# Enclosure_85x58.net
KiCad netlist of a schematic drawn in EAGLE
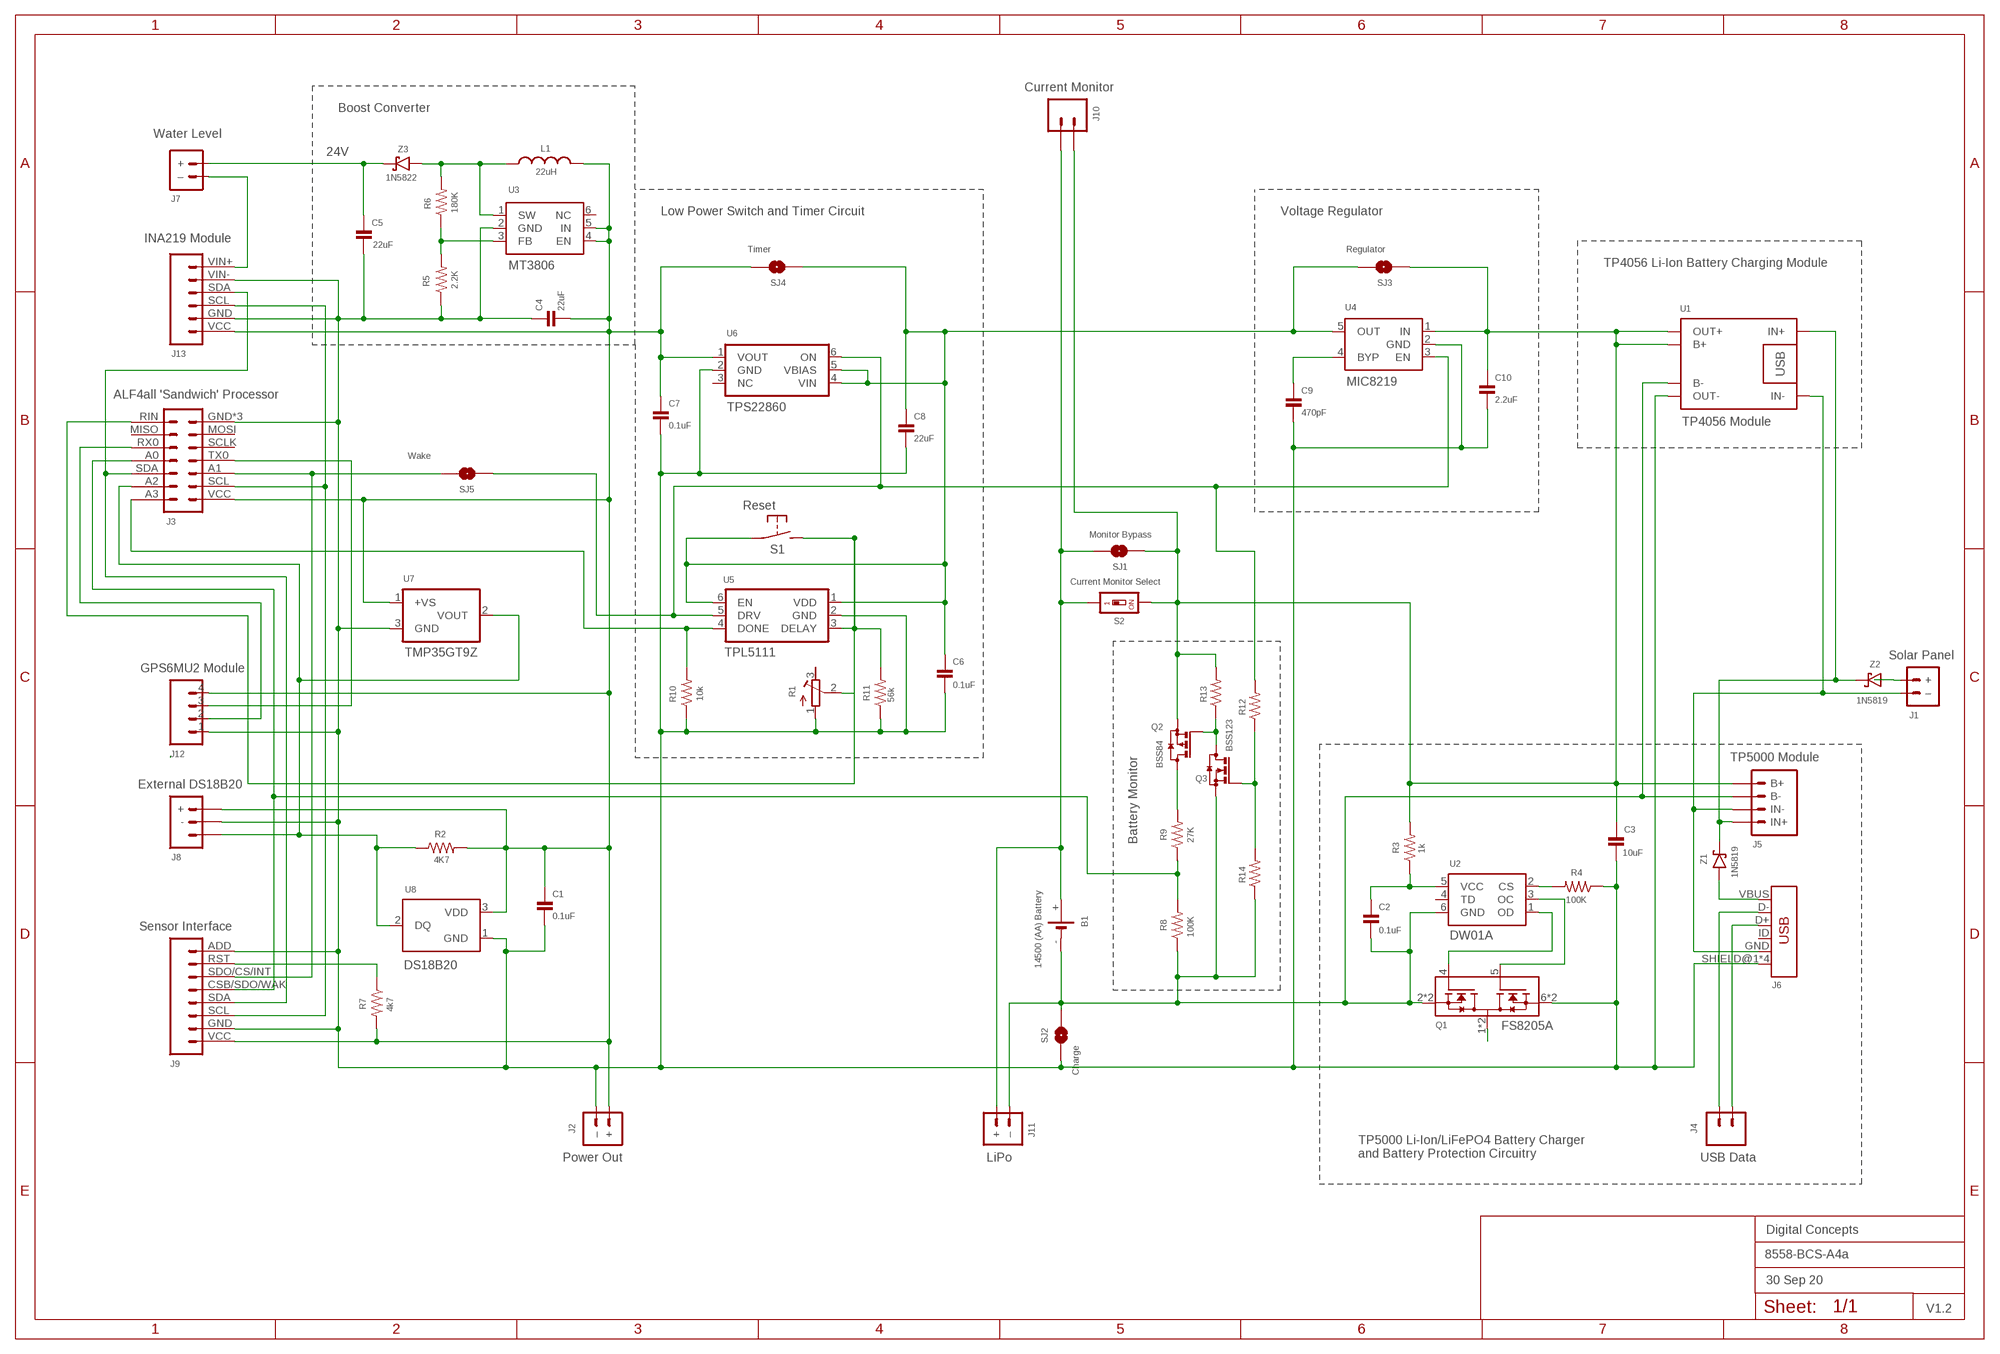
[diagram p0: schematic, sheet 1]

(export (version "E")
  (design (tool "Eeschema 10.0.6"))
  (components
    (comp (ref "B1")
      (value "14500 (AA) Battery")
      (footprint "eagle-import:BATTERY-14500")
      (libsource (lib "eagle-import") (part "BATTERY-HOLDER-14500(AA)"))
    )
    (comp (ref "C1")
      (value "0.1uF")
      (footprint "eagle-import:C0805-VIA-2")
      (libsource (lib "eagle-import") (part "CAPACITOR-VIA-2"))
    )
    (comp (ref "C2")
      (value "0.1uF")
      (footprint "eagle-import:C0805-VIA-1")
      (libsource (lib "eagle-import") (part "CAPACITOR-VIA-1"))
    )
    (comp (ref "C3")
      (value "10uF")
      (footprint "eagle-import:C0805-VIA-2")
      (libsource (lib "eagle-import") (part "CAPACITOR-VIA-2"))
    )
    (comp (ref "C4")
      (value "22uF")
      (footprint "eagle-import:C0805-VIA-1")
      (libsource (lib "eagle-import") (part "CAPACITOR-VIA-1"))
    )
    (comp (ref "C5")
      (value "22uF")
      (footprint "eagle-import:C0805")
      (libsource (lib "eagle-import") (part "CAPACITOR"))
    )
    (comp (ref "C6")
      (value "0.1uF")
      (footprint "eagle-import:C0805")
      (libsource (lib "eagle-import") (part "CAPACITOR"))
    )
    (comp (ref "C7")
      (value "0.1uF")
      (footprint "eagle-import:C0805-VIA-1")
      (libsource (lib "eagle-import") (part "CAPACITOR-VIA-1"))
    )
    (comp (ref "C8")
      (value "22uF")
      (footprint "eagle-import:C0805-VIA-2")
      (libsource (lib "eagle-import") (part "CAPACITOR-VIA-2"))
    )
    (comp (ref "C9")
      (value "470pF")
      (footprint "eagle-import:C0805")
      (libsource (lib "eagle-import") (part "CAPACITOR"))
    )
    (comp (ref "C10")
      (value "2.2uF")
      (footprint "eagle-import:C0805-VIA-2")
      (libsource (lib "eagle-import") (part "CAPACITOR-VIA-2"))
    )
    (comp (ref "J1")
      (value "Solar Panel")
      (footprint "eagle-import:JST-PH2.0-2-VERTICAL")
      (libsource (lib "eagle-import") (part "JST-PH2.0-2-MALE-VERTICAL"))
    )
    (comp (ref "J2")
      (value "Power Out")
      (footprint "eagle-import:JST-PH1.25-2")
      (libsource (lib "eagle-import") (part "JST-PH1.25-2-MALE"))
    )
    (comp (ref "J3")
      (value "ALF4all 'Sandwich' Processor")
      (footprint "eagle-import:CONN_2X7-ALF4ALL-PROCESSOR")
      (libsource (lib "eagle-import") (part "HEADER-2X7-ALF4ALL-PROCESSOR"))
    )
    (comp (ref "J4")
      (value "USB Data")
      (footprint "eagle-import:CONN_02-GENERIC")
      (libsource (lib "eagle-import") (part "1X2-PIN-HEADER"))
    )
    (comp (ref "J5")
      (value "TP5000 Module")
      (footprint "eagle-import:CONN_04-GENERIC")
      (libsource (lib "eagle-import") (part "TP5000-MODULE"))
    )
    (comp (ref "J6")
      (value "USB")
      (footprint "eagle-import:USB-MINIB")
      (libsource (lib "eagle-import") (part "USB_MINI-B_SMT"))
    )
    (comp (ref "J7")
      (value "Water Level")
      (footprint "eagle-import:JST-PH2.0-2-VERTICAL")
      (libsource (lib "eagle-import") (part "JST-PH2.0-2-MALE-VERTICAL"))
    )
    (comp (ref "J8")
      (value "External DS18B20")
      (footprint "eagle-import:JST-PH2.0-3-VERTICAL")
      (libsource (lib "eagle-import") (part "JST-PH2.0-3-MALE-VERTICAL"))
    )
    (comp (ref "J9")
      (value "Sensor Interface")
      (footprint "eagle-import:CONN_08-SENSOR")
      (libsource (lib "eagle-import") (part "HEADER-1X8-SENSOR"))
    )
    (comp (ref "J10")
      (value "Current Monitor")
      (footprint "eagle-import:JST-PH2.0-2-HORIZONTAL")
      (libsource (lib "eagle-import") (part "JST-PH2.0-2-MALE-HORIZONTALJST-PTH-2"))
    )
    (comp (ref "J11")
      (value "LiPo")
      (footprint "eagle-import:JST-PH2.0-2-VERTICAL")
      (libsource (lib "eagle-import") (part "JST-PH2.0-2-MALE-VERTICAL"))
    )
    (comp (ref "J12")
      (value "GPS6MU2 Module")
      (footprint "eagle-import:CONN_04-GENERIC")
      (libsource (lib "eagle-import") (part "HEADER-1X4-GENERIC"))
    )
    (comp (ref "J13")
      (value "INA219 Module")
      (footprint "eagle-import:CONN_06-INA219")
      (libsource (lib "eagle-import") (part "INA219-I2C-MODULE"))
    )
    (comp (ref "L1")
      (value "22uH")
      (footprint "eagle-import:L5038P")
      (libsource (lib "eagle-import") (part "INDUCTORL5038P"))
    )
    (comp (ref "Q1")
      (value "FS8205A")
      (footprint "eagle-import:SOP65P640X120-8N")
      (fields (field (name "MF") "Fortune Semiconductor"))
      (libsource (lib "eagle-import") (part "FS8205A"))
    )
    (comp (ref "Q2")
      (value "BSS84")
      (footprint "eagle-import:SOT23")
      (libsource (lib "eagle-import") (part "BSS84"))
    )
    (comp (ref "Q3")
      (value "BSS123")
      (footprint "eagle-import:SOT23")
      (libsource (lib "eagle-import") (part "BSS123"))
    )
    (comp (ref "R1")
      (value "RESISTOR-TRIMM64W")
      (footprint "eagle-import:RTRIM64W")
      (libsource (lib "eagle-import") (part "RESISTOR-TRIMM64W"))
    )
    (comp (ref "R2")
      (value "4K7")
      (footprint "eagle-import:R0805")
      (libsource (lib "eagle-import") (part "RESISTORR0805"))
    )
    (comp (ref "R3")
      (value "1k")
      (footprint "eagle-import:R0805")
      (libsource (lib "eagle-import") (part "RESISTORR0805"))
    )
    (comp (ref "R4")
      (value "100K")
      (footprint "eagle-import:R0805")
      (libsource (lib "eagle-import") (part "RESISTORR0805"))
    )
    (comp (ref "R5")
      (value "2.2K")
      (footprint "eagle-import:R0805-VIA-1")
      (libsource (lib "eagle-import") (part "RESISTOR-VIA-1"))
    )
    (comp (ref "R6")
      (value "180K")
      (footprint "eagle-import:R0805")
      (libsource (lib "eagle-import") (part "RESISTORR0805"))
    )
    (comp (ref "R7")
      (value "4k7")
      (footprint "eagle-import:R0805")
      (libsource (lib "eagle-import") (part "RESISTORR0805"))
    )
    (comp (ref "R8")
      (value "100K")
      (footprint "eagle-import:R0805")
      (libsource (lib "eagle-import") (part "RESISTORR0805"))
    )
    (comp (ref "R9")
      (value "27K")
      (footprint "eagle-import:R0805-VIA-12")
      (libsource (lib "eagle-import") (part "RESISTOR-VIA-12"))
    )
    (comp (ref "R10")
      (value "10k")
      (footprint "eagle-import:R0805-VIA-2")
      (libsource (lib "eagle-import") (part "RESISTOR-VIA-2"))
    )
    (comp (ref "R11")
      (value "56k")
      (footprint "eagle-import:R0805-VIA-1")
      (libsource (lib "eagle-import") (part "RESISTOR-VIA-1"))
    )
    (comp (ref "R12")
      (value "RESISTORR0805")
      (footprint "eagle-import:R0805")
      (libsource (lib "eagle-import") (part "RESISTORR0805"))
    )
    (comp (ref "R13")
      (value "RESISTORR0805")
      (footprint "eagle-import:R0805")
      (libsource (lib "eagle-import") (part "RESISTORR0805"))
    )
    (comp (ref "R14")
      (value "RESISTORR0805")
      (footprint "eagle-import:R0805")
      (libsource (lib "eagle-import") (part "RESISTORR0805"))
    )
    (comp (ref "S1")
      (value "Reset")
      (footprint "eagle-import:SWITCH-2-PAD-VIAS")
      (libsource (lib "eagle-import") (part "SWITCH-MOMENTARY-2-PIN-VIAS"))
    )
    (comp (ref "S2")
      (value "Current Monitor Select")
      (footprint "eagle-import:SMD-001-VIA-1")
      (libsource (lib "eagle-import") (part "SWITCH-DIP-SWS001-VIA-1"))
    )
    (comp (ref "SJ1")
      (value "Monitor Bypass")
      (footprint "eagle-import:SJ")
      (libsource (lib "eagle-import") (part "SJ"))
    )
    (comp (ref "SJ2")
      (value "Charge")
      (footprint "eagle-import:SJ-VIA-2")
      (libsource (lib "eagle-import") (part "SJ-V-2"))
    )
    (comp (ref "SJ3")
      (value "Regulator")
      (footprint "eagle-import:SJ-VIA-1")
      (libsource (lib "eagle-import") (part "SJ-V-1"))
    )
    (comp (ref "SJ4")
      (value "Timer")
      (footprint "eagle-import:SJ")
      (libsource (lib "eagle-import") (part "SJ"))
    )
    (comp (ref "SJ5")
      (value "Wake")
      (footprint "eagle-import:SJ-VIA-1")
      (libsource (lib "eagle-import") (part "SJ-V-1"))
    )
    (comp (ref "U1")
      (value "TP4056 Module")
      (footprint "eagle-import:BATTERY-CHARGER-LI-PROT")
      (libsource (lib "eagle-import") (part "BATTERY-CHARGER-LI-PROT"))
    )
    (comp (ref "U2")
      (value "DW01A")
      (footprint "eagle-import:SOT23-6")
      (fields (field (name "MF") "Fortune Semiconductor"))
      (libsource (lib "eagle-import") (part "DW01A"))
    )
    (comp (ref "U3")
      (value "MT3806")
      (footprint "eagle-import:SOT-23-6")
      (libsource (lib "eagle-import") (part "MT3806"))
    )
    (comp (ref "U4")
      (value "MIC8219")
      (footprint "eagle-import:SOT-23-5")
      (libsource (lib "eagle-import") (part "MIC5219XX"))
    )
    (comp (ref "U5")
      (value "TPL5111")
      (footprint "eagle-import:SOT-23-6")
      (libsource (lib "eagle-import") (part "TPL5111DDCR"))
    )
    (comp (ref "U6")
      (value "TPS22860")
      (footprint "eagle-import:SOT-23-6")
      (libsource (lib "eagle-import") (part "TPS22860"))
    )
    (comp (ref "U7")
      (value "TMP35GT9Z")
      (footprint "eagle-import:TO-92")
      (fields (field (name "MF") "Analog Devices"))
      (libsource (lib "eagle-import") (part "TMP35GT9Z"))
    )
    (comp (ref "U8")
      (value "DS18B20")
      (footprint "eagle-import:TO-92")
      (fields (field (name "MF") "Maxim Integrated"))
      (libsource (lib "eagle-import") (part "DS18B20"))
    )
    (comp (ref "Z1")
      (value "1N5819")
      (footprint "eagle-import:SOD-123")
      (libsource (lib "eagle-import") (part "1N5819-SOD-123"))
    )
    (comp (ref "Z2")
      (value "1N5819")
      (footprint "eagle-import:SOD-123")
      (libsource (lib "eagle-import") (part "1N5819-SOD-123"))
    )
    (comp (ref "Z3")
      (value "1N5822")
      (footprint "eagle-import:SOD-123")
      (libsource (lib "eagle-import") (part "1N5819-SOD-123"))
    )
  )
  (nets
    (net (code "1") (name "Net-(C5-Pad1)") (class "Default")
      (node (ref "C5") (pin "1") (pinfunction "1_1") (pintype "passive"))
      (node (ref "J7") (pin "+") (pinfunction "+_+") (pintype "power_in"))
      (node (ref "Z3") (pin "C") (pinfunction "C_C") (pintype "passive"))
    )
    (net (code "2") (name "Net-(J1-Pad+)") (class "Default")
      (node (ref "J1") (pin "+") (pinfunction "+_+") (pintype "power_in"))
      (node (ref "Z2") (pin "A") (pinfunction "A_A") (pintype "passive"))
    )
    (net (code "3") (name "Net-(J1-–)") (class "Default")
      (node (ref "J1") (pin "-") (pinfunction "–_-") (pintype "power_in"))
      (node (ref "J5") (pin "2") (pinfunction "IN-_2") (pintype "passive"))
      (node (ref "J6") (pin "GND") (pinfunction "GND_GND") (pintype "power_in"))
      (node (ref "U1") (pin "IN-") (pinfunction "IN-_IN-") (pintype "power_in"))
    )
    (net (code "4") (name "Net-(J3-3)") (class "Default")
      (node (ref "J3") (pin "A1") (pinfunction "3_A1") (pintype "passive"))
      (node (ref "J9") (pin "SDO/CS/INT") (pinfunction "6_SDO/CS/INT") (pintype "passive"))
      (node (ref "SJ5") (pin "1") (pinfunction "1_1") (pintype "passive"))
      (node (ref "SJ5") (pin "1@V") (pinfunction "1_1@V") (pintype "passive"))
    )
    (net (code "5") (name "Net-(J3-4)") (class "Default")
      (node (ref "J12") (pin "3") (pinfunction "3_3") (pintype "passive"))
      (node (ref "J3") (pin "TX0") (pinfunction "4_TX0") (pintype "passive"))
    )
    (net (code "6") (name "Net-(J3-8)") (class "Default")
      (node (ref "J3") (pin "RIN") (pinfunction "8_RIN") (pintype "passive"))
      (node (ref "R1") (pin "2") (pinfunction "S_2") (pintype "passive"))
      (node (ref "R11") (pin "2") (pinfunction "2_2") (pintype "passive"))
      (node (ref "S1") (pin "2") (pinfunction "S_2") (pintype "passive"))
      (node (ref "S1") (pin "2@VIA") (pinfunction "S_2@VIA") (pintype "passive"))
      (node (ref "U5") (pin "3") (pinfunction "DELAY_3") (pintype "input"))
    )
    (net (code "7") (name "Net-(J3-10)") (class "Default")
      (node (ref "J12") (pin "2") (pinfunction "2_2") (pintype "passive"))
      (node (ref "J3") (pin "RX0") (pinfunction "10_RX0") (pintype "passive"))
    )
    (net (code "8") (name "Net-(J3-11)") (class "Default")
      (node (ref "J3") (pin "A0") (pinfunction "11_A0") (pintype "passive"))
      (node (ref "J9") (pin "CSB/SDO/WAK") (pinfunction "5_CSB/SDO/WAK") (pintype "passive"))
      (node (ref "R8") (pin "2") (pinfunction "2_2") (pintype "passive"))
      (node (ref "R9") (pin "1") (pinfunction "1_1") (pintype "passive"))
      (node (ref "R9") (pin "1@VIA") (pinfunction "1_1@VIA") (pintype "passive"))
    )
    (net (code "9") (name "Net-(J3-13)") (class "Default")
      (node (ref "J3") (pin "A2") (pinfunction "13_A2") (pintype "passive"))
      (node (ref "J8") (pin "SIG") (pinfunction "SIG_SIG") (pintype "bidirectional"))
      (node (ref "R2") (pin "1") (pinfunction "1_1") (pintype "passive"))
      (node (ref "U7") (pin "2") (pinfunction "VOUT_2") (pintype "passive"))
      (node (ref "U8") (pin "2") (pinfunction "DQ_2") (pintype "bidirectional"))
    )
    (net (code "10") (name "Net-(J3-14)") (class "Default")
      (node (ref "J3") (pin "A3") (pinfunction "14_A3") (pintype "passive"))
      (node (ref "R10") (pin "2") (pinfunction "2_2") (pintype "passive"))
      (node (ref "R10") (pin "2@VIA") (pinfunction "2_2@VIA") (pintype "passive"))
      (node (ref "U5") (pin "4") (pinfunction "DONE_4") (pintype "input"))
    )
    (net (code "11") (name "Net-(J4-Pad1)") (class "Default")
      (node (ref "J4") (pin "1") (pinfunction "1_1") (pintype "passive"))
      (node (ref "J6") (pin "D-") (pinfunction "D-_D-") (pintype "bidirectional"))
    )
    (net (code "12") (name "Net-(J4-Pad2)") (class "Default")
      (node (ref "J4") (pin "2") (pinfunction "2_2") (pintype "passive"))
      (node (ref "J6") (pin "D+") (pinfunction "D+_D+") (pintype "bidirectional"))
    )
    (net (code "13") (name "Net-(J5-IN+)") (class "Default")
      (node (ref "J5") (pin "1") (pinfunction "IN+_1") (pintype "passive"))
      (node (ref "U1") (pin "IN+") (pinfunction "IN+_IN+") (pintype "power_in"))
      (node (ref "Z1") (pin "C") (pinfunction "C_C") (pintype "passive"))
      (node (ref "Z2") (pin "C") (pinfunction "C_C") (pintype "passive"))
    )
    (net (code "14") (name "Net-(J6-PadVBUS)") (class "Default")
      (node (ref "J6") (pin "VBUS") (pinfunction "VBUS_VBUS") (pintype "power_in"))
      (node (ref "Z1") (pin "A") (pinfunction "A_A") (pintype "passive"))
    )
    (net (code "15") (name "Net-(J9-7)") (class "Default")
      (node (ref "J9") (pin "RST") (pinfunction "7_RST") (pintype "passive"))
      (node (ref "R7") (pin "1") (pinfunction "1_1") (pintype "passive"))
    )
    (net (code "16") (name "Net-(J10-1)") (class "Default")
      (node (ref "C10") (pin "2") (pinfunction "2_2") (pintype "passive"))
      (node (ref "C10") (pin "2@VIA") (pinfunction "2_2@VIA") (pintype "passive"))
      (node (ref "C3") (pin "1") (pinfunction "1_1") (pintype "passive"))
      (node (ref "J10") (pin "-") (pinfunction "1_-") (pintype "passive"))
      (node (ref "J5") (pin "4") (pinfunction "B+_4") (pintype "passive"))
      (node (ref "Q2") (pin "2") (pinfunction "S_2") (pintype "passive"))
      (node (ref "R13") (pin "2") (pinfunction "2_2") (pintype "passive"))
      (node (ref "R3") (pin "2") (pinfunction "2_2") (pintype "passive"))
      (node (ref "S2") (pin "2") (pinfunction "2_2") (pintype "passive"))
      (node (ref "SJ1") (pin "2") (pinfunction "2_2") (pintype "passive"))
      (node (ref "SJ3") (pin "1") (pinfunction "1_1") (pintype "passive"))
      (node (ref "SJ3") (pin "1@V") (pinfunction "1_1@V") (pintype "passive"))
      (node (ref "U1") (pin "B+") (pinfunction "B+_B+") (pintype "power_in"))
      (node (ref "U1") (pin "OUT+") (pinfunction "OUT+_OUT+") (pintype "power_in"))
      (node (ref "U4") (pin "1") (pinfunction "IN_1") (pintype "power_in"))
    )
    (net (code "17") (name "Net-(J10-2)") (class "Default")
      (node (ref "B1") (pin "+") (pinfunction "+_+") (pintype "power_in"))
      (node (ref "J10") (pin "+") (pinfunction "2_+") (pintype "passive"))
      (node (ref "J11") (pin "+") (pinfunction "+_+") (pintype "power_in"))
      (node (ref "S2") (pin "1") (pinfunction "1_1") (pintype "passive"))
      (node (ref "S2") (pin "1@VIA") (pinfunction "1_1@VIA") (pintype "passive"))
      (node (ref "SJ1") (pin "1") (pinfunction "1_1") (pintype "passive"))
    )
    (net (code "18") (name "Net-(J11-–)") (class "Default")
      (node (ref "B1") (pin "-") (pinfunction "-_-") (pintype "power_in"))
      (node (ref "C2") (pin "2") (pinfunction "2_2") (pintype "passive"))
      (node (ref "J11") (pin "-") (pinfunction "–_-") (pintype "power_in"))
      (node (ref "J5") (pin "3") (pinfunction "B-_3") (pintype "passive"))
      (node (ref "Q1") (pin "2") (pinfunction "S1_2") (pintype "passive"))
      (node (ref "Q1") (pin "3") (pinfunction "S1_3") (pintype "passive"))
      (node (ref "Q3") (pin "2") (pinfunction "S_2") (pintype "passive"))
      (node (ref "R14") (pin "1") (pinfunction "1_1") (pintype "passive"))
      (node (ref "R8") (pin "1") (pinfunction "1_1") (pintype "passive"))
      (node (ref "SJ2") (pin "2") (pinfunction "2_2") (pintype "passive"))
      (node (ref "SJ2") (pin "2@V") (pinfunction "2_2@V") (pintype "passive"))
      (node (ref "U1") (pin "B-") (pinfunction "B-_B-") (pintype "power_in"))
      (node (ref "U2") (pin "6") (pinfunction "GND_6") (pintype "power_in"))
    )
    (net (code "19") (name "Net-(J13-1)") (class "Default")
      (node (ref "C1") (pin "1") (pinfunction "1_1") (pintype "passive"))
      (node (ref "C4") (pin "2") (pinfunction "2_2") (pintype "passive"))
      (node (ref "C7") (pin "2") (pinfunction "2_2") (pintype "passive"))
      (node (ref "J12") (pin "4") (pinfunction "4_4") (pintype "passive"))
      (node (ref "J13") (pin "VCC") (pinfunction "1_VCC") (pintype "passive"))
      (node (ref "J2") (pin "+") (pinfunction "+_+") (pintype "power_in"))
      (node (ref "J3") (pin "VCC") (pinfunction "1_VCC") (pintype "passive"))
      (node (ref "J8") (pin "+") (pinfunction "+_+") (pintype "power_in"))
      (node (ref "J9") (pin "VCC") (pinfunction "1_VCC") (pintype "passive"))
      (node (ref "L1") (pin "2") (pinfunction "2_2") (pintype "passive"))
      (node (ref "R2") (pin "2") (pinfunction "2_2") (pintype "passive"))
      (node (ref "R7") (pin "2") (pinfunction "2_2") (pintype "passive"))
      (node (ref "SJ4") (pin "1") (pinfunction "1_1") (pintype "passive"))
      (node (ref "U3") (pin "4") (pinfunction "EN_4") (pintype "input"))
      (node (ref "U3") (pin "5") (pinfunction "IN_5") (pintype "power_in"))
      (node (ref "U6") (pin "1") (pinfunction "VOUT_1") (pintype "power_in"))
      (node (ref "U7") (pin "1") (pinfunction "+VS_1") (pintype "power_in"))
      (node (ref "U8") (pin "3") (pinfunction "VDD_3") (pintype "power_in"))
    )
    (net (code "20") (name "Net-(J13-2)") (class "Default")
      (node (ref "C1") (pin "2") (pinfunction "2_2") (pintype "passive"))
      (node (ref "C1") (pin "2@VIA") (pinfunction "2_2@VIA") (pintype "passive"))
      (node (ref "C10") (pin "1") (pinfunction "1_1") (pintype "passive"))
      (node (ref "C3") (pin "2") (pinfunction "2_2") (pintype "passive"))
      (node (ref "C3") (pin "2@VIA") (pinfunction "2_2@VIA") (pintype "passive"))
      (node (ref "C4") (pin "1") (pinfunction "1_1") (pintype "passive"))
      (node (ref "C4") (pin "1@VIA") (pinfunction "1_1@VIA") (pintype "passive"))
      (node (ref "C5") (pin "2") (pinfunction "2_2") (pintype "passive"))
      (node (ref "C6") (pin "1") (pinfunction "1_1") (pintype "passive"))
      (node (ref "C7") (pin "1") (pinfunction "1_1") (pintype "passive"))
      (node (ref "C7") (pin "1@VIA") (pinfunction "1_1@VIA") (pintype "passive"))
      (node (ref "C8") (pin "2") (pinfunction "2_2") (pintype "passive"))
      (node (ref "C8") (pin "2@VIA") (pinfunction "2_2@VIA") (pintype "passive"))
      (node (ref "C9") (pin "2") (pinfunction "2_2") (pintype "passive"))
      (node (ref "J12") (pin "1") (pinfunction "1_1") (pintype "passive"))
      (node (ref "J13") (pin "GND") (pinfunction "2_GND") (pintype "passive"))
      (node (ref "J13") (pin "VIN-") (pinfunction "5_VIN-") (pintype "passive"))
      (node (ref "J2") (pin "-") (pinfunction "–_-") (pintype "power_in"))
      (node (ref "J3") (pin "GND") (pinfunction "7_GND") (pintype "passive"))
      (node (ref "J3") (pin "GND@TL") (pinfunction "7_GND@TL") (pintype "passive"))
      (node (ref "J3") (pin "GND@TR") (pinfunction "7_GND@TR") (pintype "passive"))
      (node (ref "J6") (pin "SHIELD@1") (pinfunction "SHIELD_SHIELD@1") (pintype "power_in"))
      (node (ref "J6") (pin "SHIELD@2") (pinfunction "SHIELD_SHIELD@2") (pintype "power_in"))
      (node (ref "J6") (pin "SHIELD@3") (pinfunction "SHIELD_SHIELD@3") (pintype "power_in"))
      (node (ref "J6") (pin "SHIELD@4") (pinfunction "SHIELD_SHIELD@4") (pintype "power_in"))
      (node (ref "J8") (pin "-") (pinfunction "-_-") (pintype "power_in"))
      (node (ref "J9") (pin "ADD") (pinfunction "8_ADD") (pintype "passive"))
      (node (ref "J9") (pin "GND") (pinfunction "2_GND") (pintype "passive"))
      (node (ref "Q1") (pin "6") (pinfunction "S2_6") (pintype "passive"))
      (node (ref "Q1") (pin "7") (pinfunction "S2_7") (pintype "passive"))
      (node (ref "R1") (pin "1") (pinfunction "A_1") (pintype "passive"))
      (node (ref "R10") (pin "1") (pinfunction "1_1") (pintype "passive"))
      (node (ref "R11") (pin "1") (pinfunction "1_1") (pintype "passive"))
      (node (ref "R11") (pin "1@VIA") (pinfunction "1_1@VIA") (pintype "passive"))
      (node (ref "R4") (pin "1") (pinfunction "1_1") (pintype "passive"))
      (node (ref "R5") (pin "1") (pinfunction "1_1") (pintype "passive"))
      (node (ref "R5") (pin "1@VIA") (pinfunction "1_1@VIA") (pintype "passive"))
      (node (ref "SJ2") (pin "1") (pinfunction "1_1") (pintype "passive"))
      (node (ref "SJ2") (pin "1@V") (pinfunction "1_1@V") (pintype "passive"))
      (node (ref "U1") (pin "OUT-") (pinfunction "OUT-_OUT-") (pintype "power_in"))
      (node (ref "U3") (pin "2") (pinfunction "GND_2") (pintype "power_in"))
      (node (ref "U4") (pin "2") (pinfunction "GND_2") (pintype "power_in"))
      (node (ref "U5") (pin "2") (pinfunction "GND_2") (pintype "power_in"))
      (node (ref "U6") (pin "2") (pinfunction "GND_2") (pintype "power_in"))
      (node (ref "U7") (pin "3") (pinfunction "GND_3") (pintype "passive"))
      (node (ref "U8") (pin "1") (pinfunction "GND_1") (pintype "power_in"))
    )
    (net (code "21") (name "Net-(J13-3)") (class "Default")
      (node (ref "J13") (pin "SCL") (pinfunction "3_SCL") (pintype "passive"))
      (node (ref "J3") (pin "SCL") (pinfunction "2_SCL") (pintype "passive"))
      (node (ref "J9") (pin "SCL") (pinfunction "3_SCL") (pintype "passive"))
    )
    (net (code "22") (name "Net-(J13-4)") (class "Default")
      (node (ref "J13") (pin "SDA") (pinfunction "4_SDA") (pintype "passive"))
      (node (ref "J3") (pin "SDA") (pinfunction "12_SDA") (pintype "passive"))
      (node (ref "J9") (pin "SDA") (pinfunction "4_SDA") (pintype "passive"))
    )
    (net (code "23") (name "Net-(J13-6)") (class "Default")
      (node (ref "J13") (pin "VIN+") (pinfunction "6_VIN+") (pintype "passive"))
      (node (ref "J7") (pin "-") (pinfunction "–_-") (pintype "power_in"))
    )
    (net (code "24") (name "Net-(Q1-D12-Pad1)") (class "Default")
      (node (ref "Q1") (pin "1") (pinfunction "D12_1") (pintype "passive"))
      (node (ref "Q1") (pin "8") (pinfunction "D12_8") (pintype "passive"))
    )
    (net (code "25") (name "Net-(Q1-G1)") (class "Default")
      (node (ref "Q1") (pin "4") (pinfunction "G1_4") (pintype "passive"))
      (node (ref "U2") (pin "1") (pinfunction "OD_1") (pintype "bidirectional"))
    )
    (net (code "26") (name "Net-(Q1-G2)") (class "Default")
      (node (ref "Q1") (pin "5") (pinfunction "G2_5") (pintype "passive"))
      (node (ref "U2") (pin "3") (pinfunction "OC_3") (pintype "bidirectional"))
    )
    (net (code "27") (name "Net-(Q2-D)") (class "Default")
      (node (ref "Q2") (pin "3") (pinfunction "D_3") (pintype "passive"))
      (node (ref "R9") (pin "2") (pinfunction "2_2") (pintype "passive"))
      (node (ref "R9") (pin "2@VIA") (pinfunction "2_2@VIA") (pintype "passive"))
    )
    (net (code "28") (name "Net-(Q2-G)") (class "Default")
      (node (ref "Q2") (pin "1") (pinfunction "G_1") (pintype "passive"))
      (node (ref "Q3") (pin "3") (pinfunction "D_3") (pintype "passive"))
      (node (ref "R13") (pin "1") (pinfunction "1_1") (pintype "passive"))
    )
    (net (code "29") (name "Net-(Q3-G)") (class "Default")
      (node (ref "Q3") (pin "1") (pinfunction "G_1") (pintype "passive"))
      (node (ref "R12") (pin "1") (pinfunction "1_1") (pintype "passive"))
      (node (ref "R14") (pin "2") (pinfunction "2_2") (pintype "passive"))
    )
    (net (code "30") (name "Net-(U2-CS)") (class "Default")
      (node (ref "R4") (pin "2") (pinfunction "2_2") (pintype "passive"))
      (node (ref "U2") (pin "2") (pinfunction "CS_2") (pintype "bidirectional"))
    )
    (net (code "31") (name "Net-(U2-VCC)") (class "Default")
      (node (ref "C2") (pin "1") (pinfunction "1_1") (pintype "passive"))
      (node (ref "C2") (pin "1@VIA") (pinfunction "1_1@VIA") (pintype "passive"))
      (node (ref "R3") (pin "1") (pinfunction "1_1") (pintype "passive"))
      (node (ref "U2") (pin "5") (pinfunction "VCC_5") (pintype "power_in"))
    )
    (net (code "32") (name "Net-(U3-FB)") (class "Default")
      (node (ref "R5") (pin "2") (pinfunction "2_2") (pintype "passive"))
      (node (ref "R6") (pin "1") (pinfunction "1_1") (pintype "passive"))
      (node (ref "U3") (pin "3") (pinfunction "FB_3") (pintype "input"))
    )
    (net (code "33") (name "Net-(U3-SW)") (class "Default")
      (node (ref "L1") (pin "1") (pinfunction "1_1") (pintype "passive"))
      (node (ref "R6") (pin "2") (pinfunction "2_2") (pintype "passive"))
      (node (ref "U3") (pin "1") (pinfunction "SW_1") (pintype "power_in"))
      (node (ref "Z3") (pin "A") (pinfunction "A_A") (pintype "passive"))
    )
    (net (code "34") (name "Net-(U4-BYP)") (class "Default")
      (node (ref "C9") (pin "1") (pinfunction "1_1") (pintype "passive"))
      (node (ref "U4") (pin "4") (pinfunction "BYP_4") (pintype "passive"))
    )
    (net (code "35") (name "Net-(U4-EN)") (class "Default")
      (node (ref "R12") (pin "2") (pinfunction "2_2") (pintype "passive"))
      (node (ref "SJ5") (pin "2") (pinfunction "2_2") (pintype "passive"))
      (node (ref "U4") (pin "3") (pinfunction "EN_3") (pintype "input"))
      (node (ref "U5") (pin "5") (pinfunction "DRV_5") (pintype "output"))
      (node (ref "U6") (pin "6") (pinfunction "ON_6") (pintype "input"))
    )
    (net (code "36") (name "Net-(U4-OUT)") (class "Default")
      (node (ref "C6") (pin "2") (pinfunction "2_2") (pintype "passive"))
      (node (ref "C8") (pin "1") (pinfunction "1_1") (pintype "passive"))
      (node (ref "S1") (pin "1") (pinfunction "P_1") (pintype "passive"))
      (node (ref "S1") (pin "1@VIA") (pinfunction "P_1@VIA") (pintype "passive"))
      (node (ref "SJ3") (pin "2") (pinfunction "2_2") (pintype "passive"))
      (node (ref "SJ4") (pin "2") (pinfunction "2_2") (pintype "passive"))
      (node (ref "U4") (pin "5") (pinfunction "OUT_5") (pintype "power_in"))
      (node (ref "U5") (pin "1") (pinfunction "VDD_1") (pintype "power_in"))
      (node (ref "U5") (pin "6") (pinfunction "EN_6") (pintype "input"))
      (node (ref "U6") (pin "4") (pinfunction "VIN_4") (pintype "power_in"))
      (node (ref "U6") (pin "5") (pinfunction "VBIAS_5") (pintype "input"))
    )
    (net (code "37") (name "unconnected-(J3-5-PadSCLK)") (class "Default")
      (node (ref "J3") (pin "SCLK") (pinfunction "5_SCLK") (pintype "passive"))
    )
    (net (code "38") (name "unconnected-(J3-6-PadMOSI)") (class "Default")
      (node (ref "J3") (pin "MOSI") (pinfunction "6_MOSI") (pintype "passive"))
    )
    (net (code "39") (name "unconnected-(J3-9-PadMISO)") (class "Default")
      (node (ref "J3") (pin "MISO") (pinfunction "9_MISO") (pintype "passive"))
    )
    (net (code "40") (name "unconnected-(J6-PadID)") (class "Default")
      (node (ref "J6") (pin "ID") (pinfunction "ID_ID") (pintype "bidirectional"))
    )
    (net (code "41") (name "unconnected-(R1-E-Pad3)") (class "Default")
      (node (ref "R1") (pin "3") (pinfunction "E_3") (pintype "passive"))
    )
    (net (code "42") (name "unconnected-(U2-TD-Pad4)") (class "Default")
      (node (ref "U2") (pin "4") (pinfunction "TD_4") (pintype "bidirectional"))
    )
    (net (code "43") (name "unconnected-(U3-NC-Pad6)") (class "Default")
      (node (ref "U3") (pin "6") (pinfunction "NC_6") (pintype "no_connect"))
    )
    (net (code "44") (name "unconnected-(U6-NC-Pad3)") (class "Default")
      (node (ref "U6") (pin "3") (pinfunction "NC_3") (pintype "no_connect"))
    )
  )
)
